# rs232.net
KiCad netlist of a schematic drawn in EAGLE
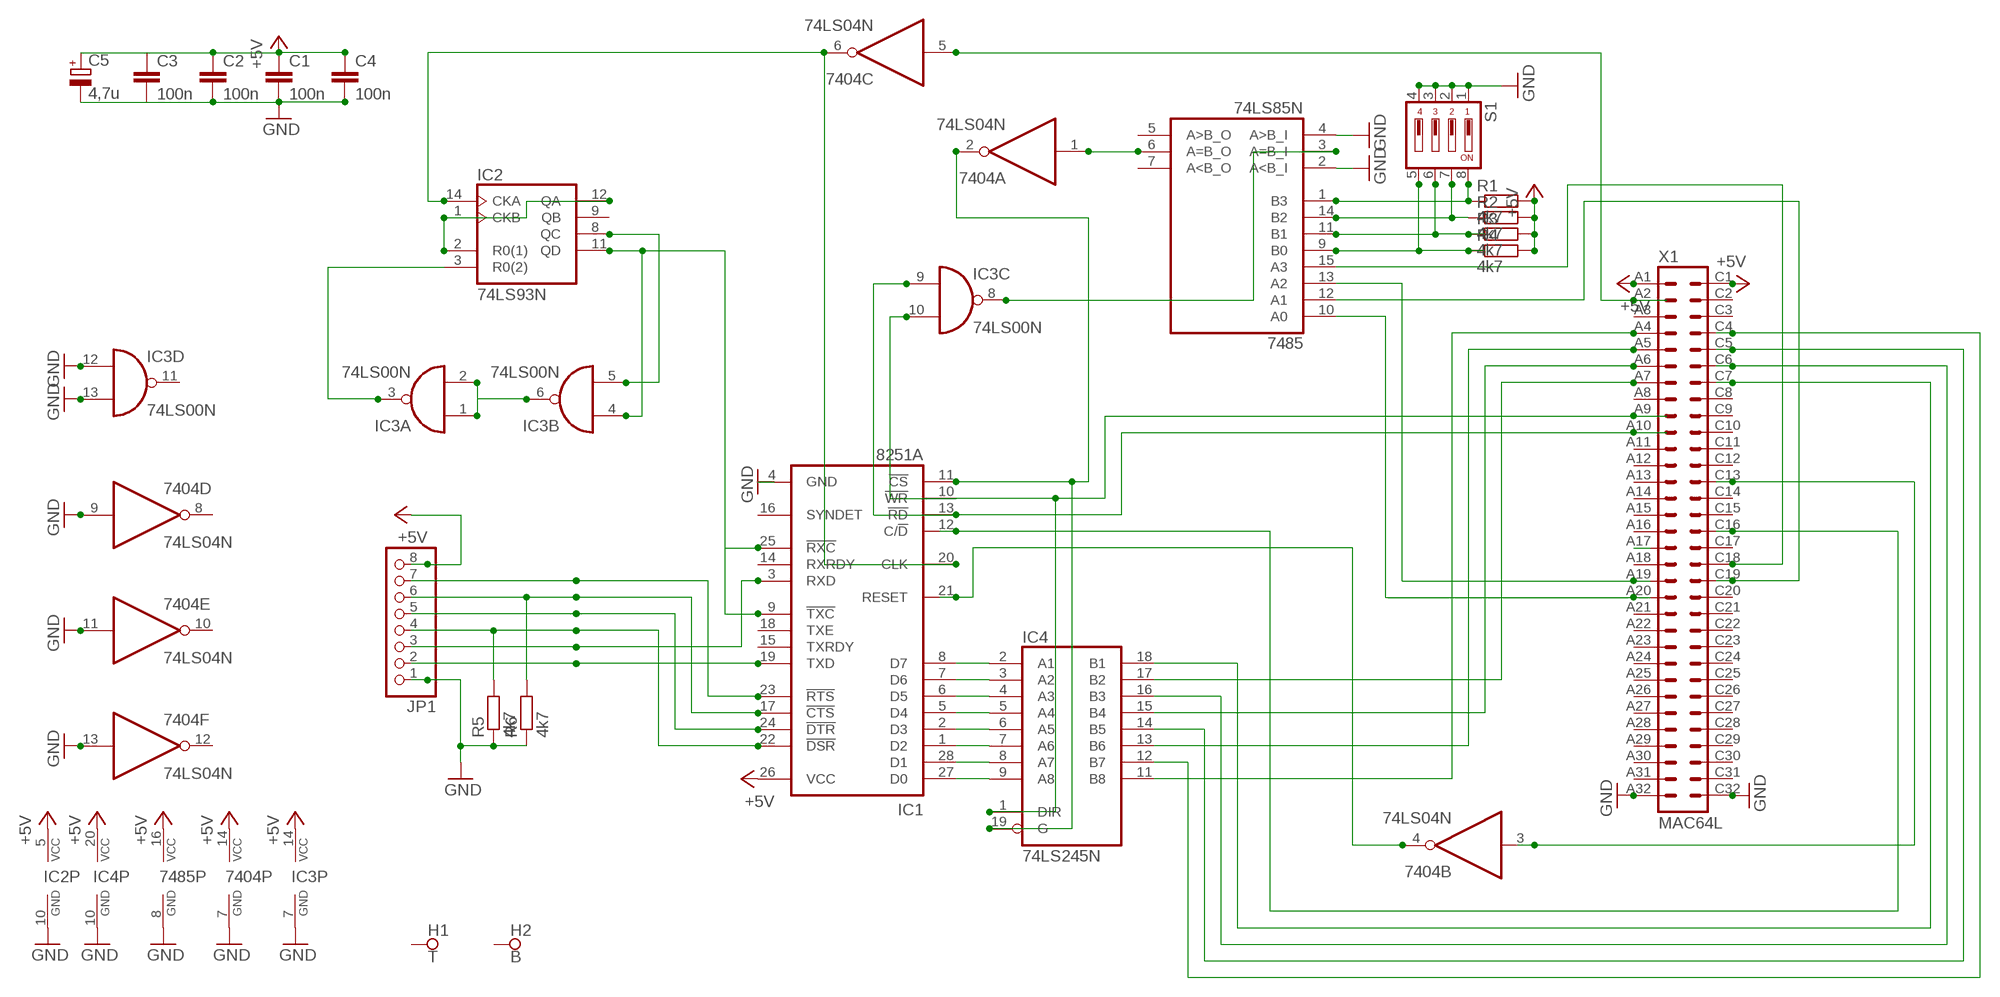
[diagram p0: schematic, sheet 1]

(export (version "E")
  (design (tool "Eeschema 10.0.6"))
  (components
    (comp (ref "7404")
      (value "74LS04N")
      (footprint "eagle-import:DIL14")
      (libsource (lib "eagle-import") (part "7404NLS"))
    )
    (comp (ref "7485")
      (value "74LS85N")
      (footprint "eagle-import:DIL16")
      (libsource (lib "eagle-import") (part "7485NLS"))
    )
    (comp (ref "C1")
      (value "100n")
      (footprint "eagle-import:C025-025X050")
      (libsource (lib "eagle-import") (part "C-EU025-025X050"))
    )
    (comp (ref "C2")
      (value "100n")
      (footprint "eagle-import:C025-025X050")
      (libsource (lib "eagle-import") (part "C-EU025-025X050"))
    )
    (comp (ref "C3")
      (value "100n")
      (footprint "eagle-import:C025-025X050")
      (libsource (lib "eagle-import") (part "C-EU025-025X050"))
    )
    (comp (ref "C4")
      (value "100n")
      (footprint "eagle-import:C025-025X050")
      (libsource (lib "eagle-import") (part "C-EU025-025X050"))
    )
    (comp (ref "C5")
      (value "4,7u")
      (footprint "eagle-import:E2,5-5")
      (libsource (lib "eagle-import") (part "CPOL-EUE2.5-5"))
    )
    (comp (ref "H1")
      (value "T")
      (footprint "eagle-import:PAD_0.1000")
      (libsource (lib "eagle-import") (part "SPECIAL_DRILL_0.1000"))
    )
    (comp (ref "H2")
      (value "B")
      (footprint "eagle-import:PAD_0.1000")
      (libsource (lib "eagle-import") (part "SPECIAL_DRILL_0.1000"))
    )
    (comp (ref "IC1")
      (value "8251A")
      (footprint "eagle-import:DIL28-6")
      (libsource (lib "eagle-import") (part "8251A"))
    )
    (comp (ref "IC2")
      (value "74LS93N")
      (footprint "eagle-import:DIL14")
      (libsource (lib "eagle-import") (part "7493NLS"))
    )
    (comp (ref "IC3")
      (value "74LS00N")
      (footprint "eagle-import:DIL14")
      (libsource (lib "eagle-import") (part "7400NLS"))
    )
    (comp (ref "IC4")
      (value "74LS245N")
      (footprint "eagle-import:DIL20")
      (libsource (lib "eagle-import") (part "74245NLS"))
    )
    (comp (ref "JP1")
      (value "PINHD-1X8")
      (footprint "eagle-import:1X08")
      (libsource (lib "eagle-import") (part "PINHD-1X8"))
    )
    (comp (ref "R1")
      (value "4k7")
      (footprint "eagle-import:0207_10")
      (libsource (lib "eagle-import") (part "R-EU_0207/10"))
    )
    (comp (ref "R2")
      (value "4k7")
      (footprint "eagle-import:0207_10")
      (libsource (lib "eagle-import") (part "R-EU_0207/10"))
    )
    (comp (ref "R3")
      (value "4k7")
      (footprint "eagle-import:0207_10")
      (libsource (lib "eagle-import") (part "R-EU_0207/10"))
    )
    (comp (ref "R4")
      (value "4k7")
      (footprint "eagle-import:0207_10")
      (libsource (lib "eagle-import") (part "R-EU_0207/10"))
    )
    (comp (ref "R5")
      (value "4k7")
      (footprint "eagle-import:0207_10")
      (libsource (lib "eagle-import") (part "R-EU_0207/10"))
    )
    (comp (ref "R6")
      (value "4k7")
      (footprint "eagle-import:0207_10")
      (libsource (lib "eagle-import") (part "R-EU_0207/10"))
    )
    (comp (ref "S1")
      (value "DS04")
      (footprint "eagle-import:DS-04")
      (libsource (lib "eagle-import") (part "DS04"))
    )
    (comp (ref "X1")
      (value "MAC64L")
      (footprint "eagle-import:MAC64L")
      (libsource (lib "eagle-import") (part "MAC64L"))
    )
  )
  (nets
    (net (code "1") (name "+5V") (class "Default")
      (node (ref "7404") (pin "14") (pinfunction "VCC_14") (pintype "power_in"))
      (node (ref "7485") (pin "16") (pinfunction "VCC_16") (pintype "power_in"))
      (node (ref "C1") (pin "1") (pinfunction "1_1") (pintype "passive"))
      (node (ref "C2") (pin "1") (pinfunction "1_1") (pintype "passive"))
      (node (ref "C3") (pin "1") (pinfunction "1_1") (pintype "passive"))
      (node (ref "C4") (pin "1") (pinfunction "1_1") (pintype "passive"))
      (node (ref "C5") (pin "+") (pinfunction "+_+") (pintype "passive"))
      (node (ref "IC1") (pin "26") (pinfunction "VCC_26") (pintype "power_in"))
      (node (ref "IC2") (pin "5") (pinfunction "VCC_5") (pintype "power_in"))
      (node (ref "IC3") (pin "14") (pinfunction "VCC_14") (pintype "power_in"))
      (node (ref "IC4") (pin "20") (pinfunction "VCC_20") (pintype "power_in"))
      (node (ref "JP1") (pin "8") (pinfunction "8_8") (pintype "passive"))
      (node (ref "R1") (pin "2") (pinfunction "2_2") (pintype "passive"))
      (node (ref "R2") (pin "2") (pinfunction "2_2") (pintype "passive"))
      (node (ref "R3") (pin "2") (pinfunction "2_2") (pintype "passive"))
      (node (ref "R4") (pin "2") (pinfunction "2_2") (pintype "passive"))
      (node (ref "X1") (pin "A1") (pinfunction "A1_A1") (pintype "passive"))
      (node (ref "X1") (pin "C1") (pinfunction "C1_C1") (pintype "passive"))
    )
    (net (code "2") (name "GND") (class "Default")
      (node (ref "7404") (pin "11") (pinfunction "I_11") (pintype "input"))
      (node (ref "7404") (pin "13") (pinfunction "I_13") (pintype "input"))
      (node (ref "7404") (pin "7") (pinfunction "GND_7") (pintype "power_in"))
      (node (ref "7404") (pin "9") (pinfunction "I_9") (pintype "input"))
      (node (ref "7485") (pin "2") (pinfunction "A<B_I_2") (pintype "input"))
      (node (ref "7485") (pin "4") (pinfunction "A>B_I_4") (pintype "input"))
      (node (ref "7485") (pin "8") (pinfunction "GND_8") (pintype "power_in"))
      (node (ref "C1") (pin "2") (pinfunction "2_2") (pintype "passive"))
      (node (ref "C2") (pin "2") (pinfunction "2_2") (pintype "passive"))
      (node (ref "C3") (pin "2") (pinfunction "2_2") (pintype "passive"))
      (node (ref "C4") (pin "2") (pinfunction "2_2") (pintype "passive"))
      (node (ref "C5") (pin "-") (pinfunction "-_-") (pintype "passive"))
      (node (ref "IC1") (pin "4") (pinfunction "GND_4") (pintype "power_in"))
      (node (ref "IC2") (pin "10") (pinfunction "GND_10") (pintype "power_in"))
      (node (ref "IC3") (pin "12") (pinfunction "I0_12") (pintype "input"))
      (node (ref "IC3") (pin "13") (pinfunction "I1_13") (pintype "input"))
      (node (ref "IC3") (pin "7") (pinfunction "GND_7") (pintype "power_in"))
      (node (ref "IC4") (pin "10") (pinfunction "GND_10") (pintype "power_in"))
      (node (ref "JP1") (pin "1") (pinfunction "1_1") (pintype "passive"))
      (node (ref "R5") (pin "1") (pinfunction "1_1") (pintype "passive"))
      (node (ref "R6") (pin "1") (pinfunction "1_1") (pintype "passive"))
      (node (ref "S1") (pin "1") (pinfunction "1_1") (pintype "passive"))
      (node (ref "S1") (pin "2") (pinfunction "2_2") (pintype "passive"))
      (node (ref "S1") (pin "3") (pinfunction "3_3") (pintype "passive"))
      (node (ref "S1") (pin "4") (pinfunction "4_4") (pintype "passive"))
      (node (ref "X1") (pin "A32") (pinfunction "A32_A32") (pintype "passive"))
      (node (ref "X1") (pin "C32") (pinfunction "C32_C32") (pintype "passive"))
    )
    (net (code "3") (name "Net-(7404A-I)") (class "Default")
      (node (ref "7404") (pin "1") (pinfunction "I_1") (pintype "input"))
      (node (ref "7485") (pin "6") (pinfunction "A=B_O_6") (pintype "output"))
    )
    (net (code "4") (name "Net-(7404A-O)") (class "Default")
      (node (ref "7404") (pin "2") (pinfunction "O_2") (pintype "output"))
      (node (ref "IC1") (pin "11") (pinfunction "~{CS}_11") (pintype "input"))
      (node (ref "IC4") (pin "19") (pinfunction "G_19") (pintype "input"))
    )
    (net (code "5") (name "Net-(7404B-I)") (class "Default")
      (node (ref "7404") (pin "3") (pinfunction "I_3") (pintype "input"))
      (node (ref "X1") (pin "C13") (pinfunction "C13_C13") (pintype "passive"))
    )
    (net (code "6") (name "Net-(7404B-O)") (class "Default")
      (node (ref "7404") (pin "4") (pinfunction "O_4") (pintype "output"))
      (node (ref "IC1") (pin "21") (pinfunction "RESET_21") (pintype "input"))
    )
    (net (code "7") (name "Net-(7404C-I)") (class "Default")
      (node (ref "7404") (pin "5") (pinfunction "I_5") (pintype "input"))
      (node (ref "X1") (pin "A2") (pinfunction "A2_A2") (pintype "passive"))
    )
    (net (code "8") (name "Net-(7404C-O)") (class "Default")
      (node (ref "7404") (pin "6") (pinfunction "O_6") (pintype "output"))
      (node (ref "IC1") (pin "20") (pinfunction "CLK_20") (pintype "input"))
      (node (ref "IC2") (pin "14") (pinfunction "CKA_14") (pintype "input"))
    )
    (net (code "9") (name "Net-(7485A-A0)") (class "Default")
      (node (ref "7485") (pin "10") (pinfunction "A0_10") (pintype "input"))
      (node (ref "X1") (pin "A20") (pinfunction "A20_A20") (pintype "passive"))
    )
    (net (code "10") (name "Net-(7485A-A1)") (class "Default")
      (node (ref "7485") (pin "12") (pinfunction "A1_12") (pintype "input"))
      (node (ref "X1") (pin "C19") (pinfunction "C19_C19") (pintype "passive"))
    )
    (net (code "11") (name "Net-(7485A-A2)") (class "Default")
      (node (ref "7485") (pin "13") (pinfunction "A2_13") (pintype "input"))
      (node (ref "X1") (pin "A19") (pinfunction "A19_A19") (pintype "passive"))
    )
    (net (code "12") (name "Net-(7485A-A3)") (class "Default")
      (node (ref "7485") (pin "15") (pinfunction "A3_15") (pintype "input"))
      (node (ref "X1") (pin "C18") (pinfunction "C18_C18") (pintype "passive"))
    )
    (net (code "13") (name "Net-(7485A-A=B_I)") (class "Default")
      (node (ref "7485") (pin "3") (pinfunction "A=B_I_3") (pintype "input"))
      (node (ref "IC3") (pin "8") (pinfunction "O_8") (pintype "output"))
    )
    (net (code "14") (name "Net-(7485A-B0)") (class "Default")
      (node (ref "7485") (pin "9") (pinfunction "B0_9") (pintype "input"))
      (node (ref "R4") (pin "1") (pinfunction "1_1") (pintype "passive"))
      (node (ref "S1") (pin "5") (pinfunction "5_5") (pintype "passive"))
    )
    (net (code "15") (name "Net-(7485A-B1)") (class "Default")
      (node (ref "7485") (pin "11") (pinfunction "B1_11") (pintype "input"))
      (node (ref "R3") (pin "1") (pinfunction "1_1") (pintype "passive"))
      (node (ref "S1") (pin "6") (pinfunction "6_6") (pintype "passive"))
    )
    (net (code "16") (name "Net-(7485A-B2)") (class "Default")
      (node (ref "7485") (pin "14") (pinfunction "B2_14") (pintype "input"))
      (node (ref "R2") (pin "1") (pinfunction "1_1") (pintype "passive"))
      (node (ref "S1") (pin "7") (pinfunction "7_7") (pintype "passive"))
    )
    (net (code "17") (name "Net-(7485A-B3)") (class "Default")
      (node (ref "7485") (pin "1") (pinfunction "B3_1") (pintype "input"))
      (node (ref "R1") (pin "1") (pinfunction "1_1") (pintype "passive"))
      (node (ref "S1") (pin "8") (pinfunction "8_8") (pintype "passive"))
    )
    (net (code "18") (name "Net-(IC1-C{slash}~{D})") (class "Default")
      (node (ref "IC1") (pin "12") (pinfunction "C/~{D}_12") (pintype "input"))
      (node (ref "X1") (pin "C16") (pinfunction "C16_C16") (pintype "passive"))
    )
    (net (code "19") (name "Net-(IC1-D0)") (class "Default")
      (node (ref "IC1") (pin "27") (pinfunction "D0_27") (pintype "tri_state"))
      (node (ref "IC4") (pin "9") (pinfunction "A8_9") (pintype "bidirectional"))
    )
    (net (code "20") (name "Net-(IC1-D1)") (class "Default")
      (node (ref "IC1") (pin "28") (pinfunction "D1_28") (pintype "tri_state"))
      (node (ref "IC4") (pin "8") (pinfunction "A7_8") (pintype "bidirectional"))
    )
    (net (code "21") (name "Net-(IC1-D2)") (class "Default")
      (node (ref "IC1") (pin "1") (pinfunction "D2_1") (pintype "tri_state"))
      (node (ref "IC4") (pin "7") (pinfunction "A6_7") (pintype "bidirectional"))
    )
    (net (code "22") (name "Net-(IC1-D3)") (class "Default")
      (node (ref "IC1") (pin "2") (pinfunction "D3_2") (pintype "tri_state"))
      (node (ref "IC4") (pin "6") (pinfunction "A5_6") (pintype "bidirectional"))
    )
    (net (code "23") (name "Net-(IC1-D4)") (class "Default")
      (node (ref "IC1") (pin "5") (pinfunction "D4_5") (pintype "tri_state"))
      (node (ref "IC4") (pin "5") (pinfunction "A4_5") (pintype "bidirectional"))
    )
    (net (code "24") (name "Net-(IC1-D5)") (class "Default")
      (node (ref "IC1") (pin "6") (pinfunction "D5_6") (pintype "tri_state"))
      (node (ref "IC4") (pin "4") (pinfunction "A3_4") (pintype "bidirectional"))
    )
    (net (code "25") (name "Net-(IC1-D6)") (class "Default")
      (node (ref "IC1") (pin "7") (pinfunction "D6_7") (pintype "tri_state"))
      (node (ref "IC4") (pin "3") (pinfunction "A2_3") (pintype "bidirectional"))
    )
    (net (code "26") (name "Net-(IC1-D7)") (class "Default")
      (node (ref "IC1") (pin "8") (pinfunction "D7_8") (pintype "tri_state"))
      (node (ref "IC4") (pin "2") (pinfunction "A1_2") (pintype "bidirectional"))
    )
    (net (code "27") (name "Net-(IC1-RXD)") (class "Default")
      (node (ref "IC1") (pin "3") (pinfunction "RXD_3") (pintype "input"))
      (node (ref "JP1") (pin "3") (pinfunction "3_3") (pintype "passive"))
    )
    (net (code "28") (name "Net-(IC1-TXD)") (class "Default")
      (node (ref "IC1") (pin "19") (pinfunction "TXD_19") (pintype "output"))
      (node (ref "JP1") (pin "2") (pinfunction "2_2") (pintype "passive"))
    )
    (net (code "29") (name "Net-(IC1-~{CTS})") (class "Default")
      (node (ref "IC1") (pin "17") (pinfunction "~{CTS}_17") (pintype "input"))
      (node (ref "JP1") (pin "6") (pinfunction "6_6") (pintype "passive"))
      (node (ref "R6") (pin "2") (pinfunction "2_2") (pintype "passive"))
    )
    (net (code "30") (name "Net-(IC1-~{DSR})") (class "Default")
      (node (ref "IC1") (pin "22") (pinfunction "~{DSR}_22") (pintype "input"))
      (node (ref "JP1") (pin "4") (pinfunction "4_4") (pintype "passive"))
      (node (ref "R5") (pin "2") (pinfunction "2_2") (pintype "passive"))
    )
    (net (code "31") (name "Net-(IC1-~{DTR})") (class "Default")
      (node (ref "IC1") (pin "24") (pinfunction "~{DTR}_24") (pintype "output"))
      (node (ref "JP1") (pin "5") (pinfunction "5_5") (pintype "passive"))
    )
    (net (code "32") (name "Net-(IC1-~{RD})") (class "Default")
      (node (ref "IC1") (pin "13") (pinfunction "~{RD}_13") (pintype "input"))
      (node (ref "IC3") (pin "9") (pinfunction "I0_9") (pintype "input"))
      (node (ref "X1") (pin "A10") (pinfunction "A10_A10") (pintype "passive"))
    )
    (net (code "33") (name "Net-(IC1-~{RTS})") (class "Default")
      (node (ref "IC1") (pin "23") (pinfunction "~{RTS}_23") (pintype "output"))
      (node (ref "JP1") (pin "7") (pinfunction "7_7") (pintype "passive"))
    )
    (net (code "34") (name "Net-(IC1-~{RXC})") (class "Default")
      (node (ref "IC1") (pin "25") (pinfunction "~{RXC}_25") (pintype "input"))
      (node (ref "IC1") (pin "9") (pinfunction "~{TXC}_9") (pintype "input"))
      (node (ref "IC2") (pin "11") (pinfunction "QD_11") (pintype "output"))
      (node (ref "IC3") (pin "4") (pinfunction "I0_4") (pintype "input"))
    )
    (net (code "35") (name "Net-(IC1-~{WR})") (class "Default")
      (node (ref "IC1") (pin "10") (pinfunction "~{WR}_10") (pintype "input"))
      (node (ref "IC3") (pin "10") (pinfunction "I1_10") (pintype "input"))
      (node (ref "IC4") (pin "1") (pinfunction "DIR_1") (pintype "input"))
      (node (ref "X1") (pin "A9") (pinfunction "A9_A9") (pintype "passive"))
    )
    (net (code "36") (name "Net-(IC2A-CKB)") (class "Default")
      (node (ref "IC2") (pin "1") (pinfunction "CKB_1") (pintype "input"))
      (node (ref "IC2") (pin "12") (pinfunction "QA_12") (pintype "output"))
      (node (ref "IC2") (pin "2") (pinfunction "R0(1)_2") (pintype "input"))
    )
    (net (code "37") (name "Net-(IC2A-QC)") (class "Default")
      (node (ref "IC2") (pin "8") (pinfunction "QC_8") (pintype "output"))
      (node (ref "IC3") (pin "5") (pinfunction "I1_5") (pintype "input"))
    )
    (net (code "38") (name "Net-(IC2A-R0(2))") (class "Default")
      (node (ref "IC2") (pin "3") (pinfunction "R0(2)_3") (pintype "input"))
      (node (ref "IC3") (pin "3") (pinfunction "O_3") (pintype "output"))
    )
    (net (code "39") (name "Net-(IC3A-I0)") (class "Default")
      (node (ref "IC3") (pin "1") (pinfunction "I0_1") (pintype "input"))
      (node (ref "IC3") (pin "2") (pinfunction "I1_2") (pintype "input"))
      (node (ref "IC3") (pin "6") (pinfunction "O_6") (pintype "output"))
    )
    (net (code "40") (name "Net-(IC4A-B1)") (class "Default")
      (node (ref "IC4") (pin "18") (pinfunction "B1_18") (pintype "bidirectional"))
      (node (ref "X1") (pin "C7") (pinfunction "C7_C7") (pintype "passive"))
    )
    (net (code "41") (name "Net-(IC4A-B2)") (class "Default")
      (node (ref "IC4") (pin "17") (pinfunction "B2_17") (pintype "bidirectional"))
      (node (ref "X1") (pin "A7") (pinfunction "A7_A7") (pintype "passive"))
    )
    (net (code "42") (name "Net-(IC4A-B3)") (class "Default")
      (node (ref "IC4") (pin "16") (pinfunction "B3_16") (pintype "bidirectional"))
      (node (ref "X1") (pin "C6") (pinfunction "C6_C6") (pintype "passive"))
    )
    (net (code "43") (name "Net-(IC4A-B4)") (class "Default")
      (node (ref "IC4") (pin "15") (pinfunction "B4_15") (pintype "bidirectional"))
      (node (ref "X1") (pin "A6") (pinfunction "A6_A6") (pintype "passive"))
    )
    (net (code "44") (name "Net-(IC4A-B5)") (class "Default")
      (node (ref "IC4") (pin "14") (pinfunction "B5_14") (pintype "bidirectional"))
      (node (ref "X1") (pin "C5") (pinfunction "C5_C5") (pintype "passive"))
    )
    (net (code "45") (name "Net-(IC4A-B6)") (class "Default")
      (node (ref "IC4") (pin "13") (pinfunction "B6_13") (pintype "bidirectional"))
      (node (ref "X1") (pin "A5") (pinfunction "A5_A5") (pintype "passive"))
    )
    (net (code "46") (name "Net-(IC4A-B7)") (class "Default")
      (node (ref "IC4") (pin "12") (pinfunction "B7_12") (pintype "bidirectional"))
      (node (ref "X1") (pin "C4") (pinfunction "C4_C4") (pintype "passive"))
    )
    (net (code "47") (name "Net-(IC4A-B8)") (class "Default")
      (node (ref "IC4") (pin "11") (pinfunction "B8_11") (pintype "bidirectional"))
      (node (ref "X1") (pin "A4") (pinfunction "A4_A4") (pintype "passive"))
    )
    (net (code "48") (name "unconnected-(7404D-O-Pad8)") (class "Default")
      (node (ref "7404") (pin "8") (pinfunction "O_8") (pintype "output"))
    )
    (net (code "49") (name "unconnected-(7404E-O-Pad10)") (class "Default")
      (node (ref "7404") (pin "10") (pinfunction "O_10") (pintype "output"))
    )
    (net (code "50") (name "unconnected-(7404F-O-Pad12)") (class "Default")
      (node (ref "7404") (pin "12") (pinfunction "O_12") (pintype "output"))
    )
    (net (code "51") (name "unconnected-(7485A-A<B_O-Pad7)") (class "Default")
      (node (ref "7485") (pin "7") (pinfunction "A<B_O_7") (pintype "output"))
    )
    (net (code "52") (name "unconnected-(7485A-A>B_O-Pad5)") (class "Default")
      (node (ref "7485") (pin "5") (pinfunction "A>B_O_5") (pintype "output"))
    )
    (net (code "53") (name "unconnected-(H1-Pad1)") (class "Default")
      (node (ref "H1") (pin "1") (pinfunction "1_1") (pintype "passive"))
    )
    (net (code "54") (name "unconnected-(H2-Pad1)") (class "Default")
      (node (ref "H2") (pin "1") (pinfunction "1_1") (pintype "passive"))
    )
    (net (code "55") (name "unconnected-(IC1-RXRDY-Pad14)") (class "Default")
      (node (ref "IC1") (pin "14") (pinfunction "RXRDY_14") (pintype "output"))
    )
    (net (code "56") (name "unconnected-(IC1-SYNDET-Pad16)") (class "Default")
      (node (ref "IC1") (pin "16") (pinfunction "SYNDET_16") (pintype "bidirectional"))
    )
    (net (code "57") (name "unconnected-(IC1-TXE-Pad18)") (class "Default")
      (node (ref "IC1") (pin "18") (pinfunction "TXE_18") (pintype "output"))
    )
    (net (code "58") (name "unconnected-(IC1-TXRDY-Pad15)") (class "Default")
      (node (ref "IC1") (pin "15") (pinfunction "TXRDY_15") (pintype "output"))
    )
    (net (code "59") (name "unconnected-(IC2A-QB-Pad9)") (class "Default")
      (node (ref "IC2") (pin "9") (pinfunction "QB_9") (pintype "output"))
    )
    (net (code "60") (name "unconnected-(IC3D-O-Pad11)") (class "Default")
      (node (ref "IC3") (pin "11") (pinfunction "O_11") (pintype "output"))
    )
    (net (code "61") (name "unconnected-(X1-PadA3)") (class "Default")
      (node (ref "X1") (pin "A3") (pinfunction "A3_A3") (pintype "passive"))
    )
    (net (code "62") (name "unconnected-(X1-PadA8)") (class "Default")
      (node (ref "X1") (pin "A8") (pinfunction "A8_A8") (pintype "passive"))
    )
    (net (code "63") (name "unconnected-(X1-PadA11)") (class "Default")
      (node (ref "X1") (pin "A11") (pinfunction "A11_A11") (pintype "passive"))
    )
    (net (code "64") (name "unconnected-(X1-PadA12)") (class "Default")
      (node (ref "X1") (pin "A12") (pinfunction "A12_A12") (pintype "passive"))
    )
    (net (code "65") (name "unconnected-(X1-PadA13)") (class "Default")
      (node (ref "X1") (pin "A13") (pinfunction "A13_A13") (pintype "passive"))
    )
    (net (code "66") (name "unconnected-(X1-PadA14)") (class "Default")
      (node (ref "X1") (pin "A14") (pinfunction "A14_A14") (pintype "passive"))
    )
    (net (code "67") (name "unconnected-(X1-PadA15)") (class "Default")
      (node (ref "X1") (pin "A15") (pinfunction "A15_A15") (pintype "passive"))
    )
    (net (code "68") (name "unconnected-(X1-PadA16)") (class "Default")
      (node (ref "X1") (pin "A16") (pinfunction "A16_A16") (pintype "passive"))
    )
    (net (code "69") (name "unconnected-(X1-PadA17)") (class "Default")
      (node (ref "X1") (pin "A17") (pinfunction "A17_A17") (pintype "passive"))
    )
    (net (code "70") (name "unconnected-(X1-PadA18)") (class "Default")
      (node (ref "X1") (pin "A18") (pinfunction "A18_A18") (pintype "passive"))
    )
    (net (code "71") (name "unconnected-(X1-PadA21)") (class "Default")
      (node (ref "X1") (pin "A21") (pinfunction "A21_A21") (pintype "passive"))
    )
    (net (code "72") (name "unconnected-(X1-PadA22)") (class "Default")
      (node (ref "X1") (pin "A22") (pinfunction "A22_A22") (pintype "passive"))
    )
    (net (code "73") (name "unconnected-(X1-PadA23)") (class "Default")
      (node (ref "X1") (pin "A23") (pinfunction "A23_A23") (pintype "passive"))
    )
    (net (code "74") (name "unconnected-(X1-PadA24)") (class "Default")
      (node (ref "X1") (pin "A24") (pinfunction "A24_A24") (pintype "passive"))
    )
    (net (code "75") (name "unconnected-(X1-PadA25)") (class "Default")
      (node (ref "X1") (pin "A25") (pinfunction "A25_A25") (pintype "passive"))
    )
    (net (code "76") (name "unconnected-(X1-PadA26)") (class "Default")
      (node (ref "X1") (pin "A26") (pinfunction "A26_A26") (pintype "passive"))
    )
    (net (code "77") (name "unconnected-(X1-PadA27)") (class "Default")
      (node (ref "X1") (pin "A27") (pinfunction "A27_A27") (pintype "passive"))
    )
    (net (code "78") (name "unconnected-(X1-PadA28)") (class "Default")
      (node (ref "X1") (pin "A28") (pinfunction "A28_A28") (pintype "passive"))
    )
    (net (code "79") (name "unconnected-(X1-PadA29)") (class "Default")
      (node (ref "X1") (pin "A29") (pinfunction "A29_A29") (pintype "passive"))
    )
    (net (code "80") (name "unconnected-(X1-PadA30)") (class "Default")
      (node (ref "X1") (pin "A30") (pinfunction "A30_A30") (pintype "passive"))
    )
    (net (code "81") (name "unconnected-(X1-PadA31)") (class "Default")
      (node (ref "X1") (pin "A31") (pinfunction "A31_A31") (pintype "passive"))
    )
    (net (code "82") (name "unconnected-(X1-PadC2)") (class "Default")
      (node (ref "X1") (pin "C2") (pinfunction "C2_C2") (pintype "passive"))
    )
    (net (code "83") (name "unconnected-(X1-PadC3)") (class "Default")
      (node (ref "X1") (pin "C3") (pinfunction "C3_C3") (pintype "passive"))
    )
    (net (code "84") (name "unconnected-(X1-PadC8)") (class "Default")
      (node (ref "X1") (pin "C8") (pinfunction "C8_C8") (pintype "passive"))
    )
    (net (code "85") (name "unconnected-(X1-PadC9)") (class "Default")
      (node (ref "X1") (pin "C9") (pinfunction "C9_C9") (pintype "passive"))
    )
    (net (code "86") (name "unconnected-(X1-PadC10)") (class "Default")
      (node (ref "X1") (pin "C10") (pinfunction "C10_C10") (pintype "passive"))
    )
    (net (code "87") (name "unconnected-(X1-PadC11)") (class "Default")
      (node (ref "X1") (pin "C11") (pinfunction "C11_C11") (pintype "passive"))
    )
    (net (code "88") (name "unconnected-(X1-PadC12)") (class "Default")
      (node (ref "X1") (pin "C12") (pinfunction "C12_C12") (pintype "passive"))
    )
    (net (code "89") (name "unconnected-(X1-PadC14)") (class "Default")
      (node (ref "X1") (pin "C14") (pinfunction "C14_C14") (pintype "passive"))
    )
    (net (code "90") (name "unconnected-(X1-PadC15)") (class "Default")
      (node (ref "X1") (pin "C15") (pinfunction "C15_C15") (pintype "passive"))
    )
    (net (code "91") (name "unconnected-(X1-PadC17)") (class "Default")
      (node (ref "X1") (pin "C17") (pinfunction "C17_C17") (pintype "passive"))
    )
    (net (code "92") (name "unconnected-(X1-PadC20)") (class "Default")
      (node (ref "X1") (pin "C20") (pinfunction "C20_C20") (pintype "passive"))
    )
    (net (code "93") (name "unconnected-(X1-PadC21)") (class "Default")
      (node (ref "X1") (pin "C21") (pinfunction "C21_C21") (pintype "passive"))
    )
    (net (code "94") (name "unconnected-(X1-PadC22)") (class "Default")
      (node (ref "X1") (pin "C22") (pinfunction "C22_C22") (pintype "passive"))
    )
    (net (code "95") (name "unconnected-(X1-PadC23)") (class "Default")
      (node (ref "X1") (pin "C23") (pinfunction "C23_C23") (pintype "passive"))
    )
    (net (code "96") (name "unconnected-(X1-PadC24)") (class "Default")
      (node (ref "X1") (pin "C24") (pinfunction "C24_C24") (pintype "passive"))
    )
    (net (code "97") (name "unconnected-(X1-PadC25)") (class "Default")
      (node (ref "X1") (pin "C25") (pinfunction "C25_C25") (pintype "passive"))
    )
    (net (code "98") (name "unconnected-(X1-PadC26)") (class "Default")
      (node (ref "X1") (pin "C26") (pinfunction "C26_C26") (pintype "passive"))
    )
    (net (code "99") (name "unconnected-(X1-PadC27)") (class "Default")
      (node (ref "X1") (pin "C27") (pinfunction "C27_C27") (pintype "passive"))
    )
    (net (code "100") (name "unconnected-(X1-PadC28)") (class "Default")
      (node (ref "X1") (pin "C28") (pinfunction "C28_C28") (pintype "passive"))
    )
    (net (code "101") (name "unconnected-(X1-PadC29)") (class "Default")
      (node (ref "X1") (pin "C29") (pinfunction "C29_C29") (pintype "passive"))
    )
    (net (code "102") (name "unconnected-(X1-PadC30)") (class "Default")
      (node (ref "X1") (pin "C30") (pinfunction "C30_C30") (pintype "passive"))
    )
    (net (code "103") (name "unconnected-(X1-PadC31)") (class "Default")
      (node (ref "X1") (pin "C31") (pinfunction "C31_C31") (pintype "passive"))
    )
  )
)
